# MEGA2560_Rev3e_1.net
KiCad netlist of a schematic drawn in Altium Designer
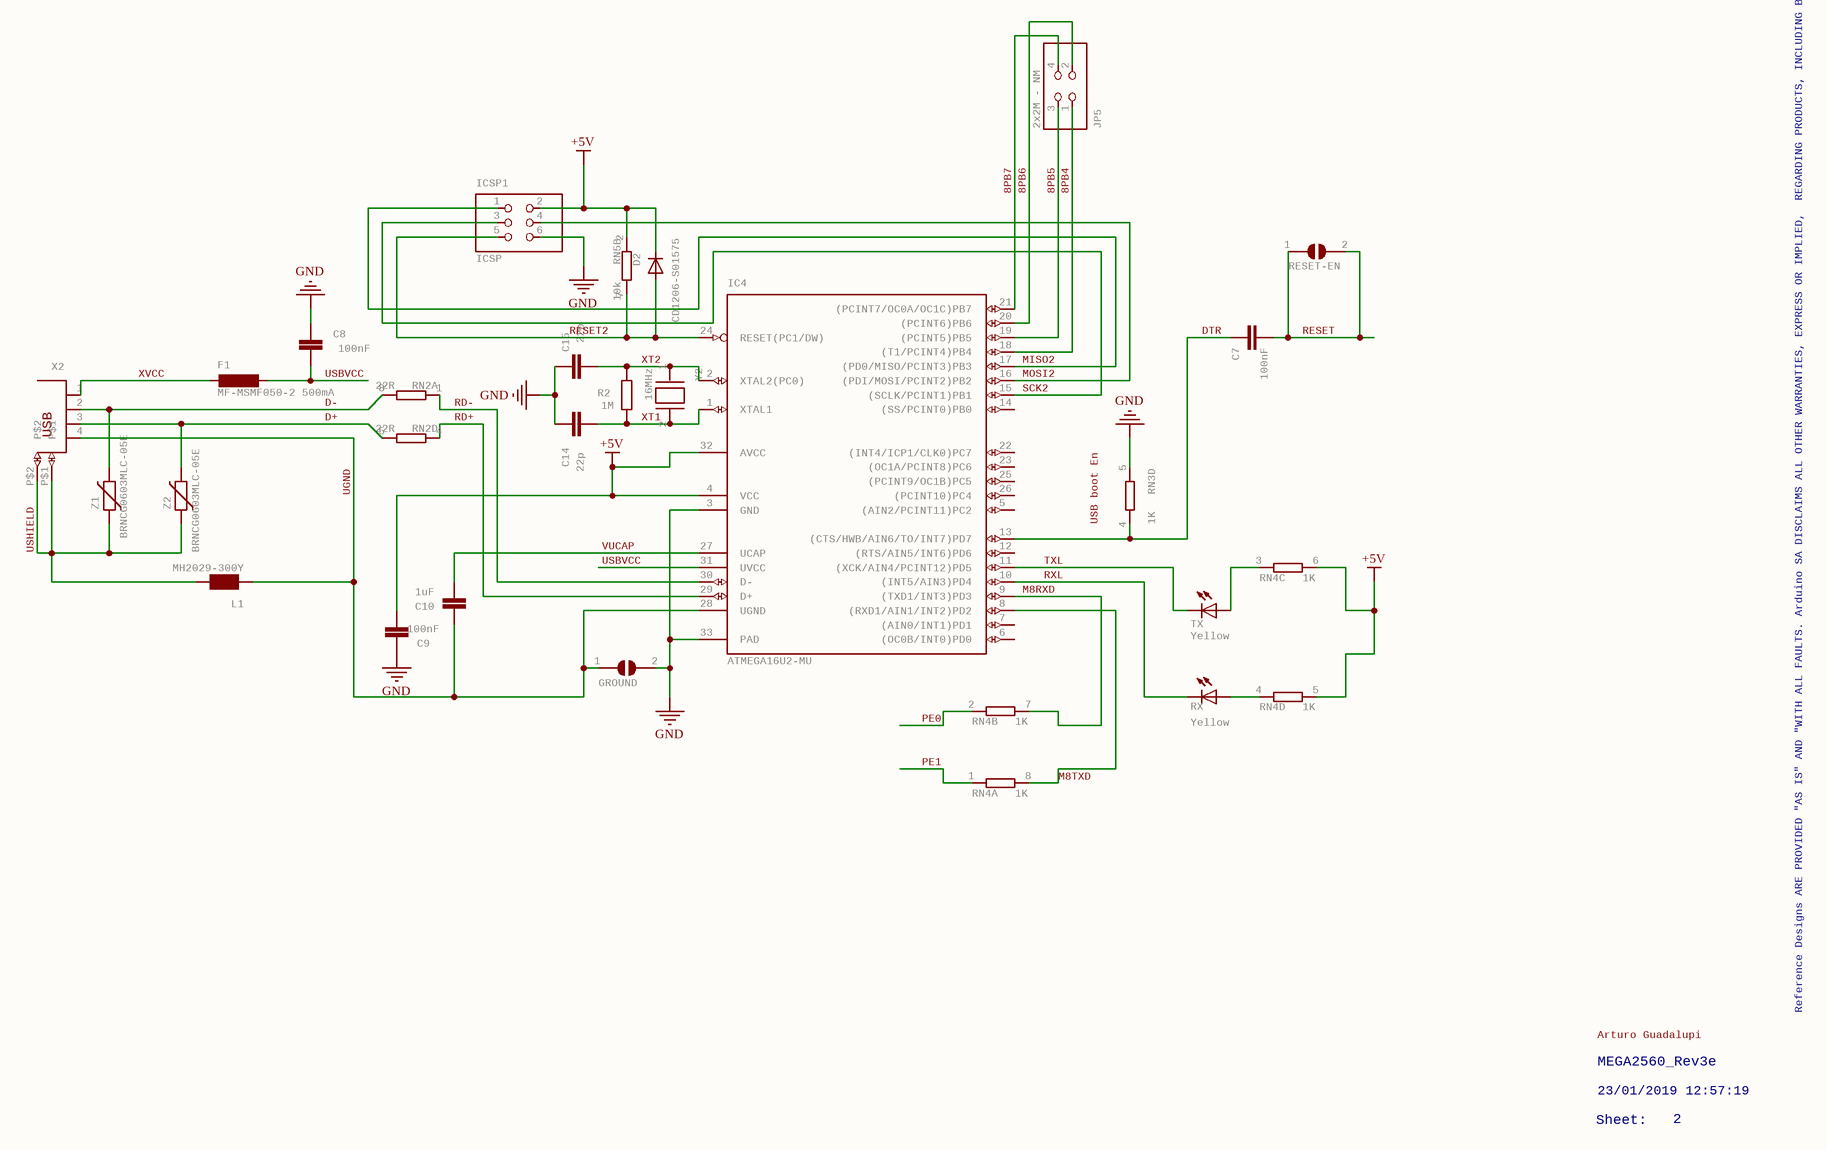
[diagram p0: MEGA2560_Rev3e_1.SchDoc]

(export (version "E")
  (design (tool "Eeschema 10.0.6"))
  (components
    (comp (ref "C7")
      (value "100nF")
      (footprint "C0603-ROUND")
      (description "100nF 0603 50V")
      (fields (field (name "PART_NUMBER") "cl10b104kbnc"))
      (libsource (lib "Condensatori") (part "0015_100NF_0603"))
    )
    (comp (ref "C8")
      (value "100nF")
      (footprint "C0603-ROUND")
      (description "100nF 0603 50V")
      (fields (field (name "PART_NUMBER") "cl10b104kbnc"))
      (libsource (lib "Condensatori") (part "0015_100NF_0603"))
    )
    (comp (ref "C9")
      (value "100nF")
      (footprint "C0603-ROUND")
      (description "100nF 0603 50V")
      (fields (field (name "PART_NUMBER") "cl10b104kbnc"))
      (libsource (lib "") (part "0015_100NF_0603_1"))
    )
    (comp (ref "C10")
      (value "1uF")
      (footprint "C0603-ROUND")
      (description "1uF 0603")
      (fields (field (name "PART_NUMBER") "1uF_0603/GRM188R61E105KA12D"))
      (libsource (lib "Condensatori") (part "0006_1UF_0603/GRM188R61E105KA12D"))
    )
    (comp (ref "C14")
      (value "22p")
      (footprint "C0603-ROUND")
      (description "22pF 0603")
      (fields (field (name "PART_NUMBER") "22pF_0603"))
      (libsource (lib "Condensatori") (part "0014_22PF_0603"))
    )
    (comp (ref "C15")
      (value "22p")
      (footprint "C0603-ROUND")
      (description "22pF 0603")
      (fields (field (name "PART_NUMBER") "22pF_0603"))
      (libsource (lib "Condensatori") (part "0014_22PF_0603"))
    )
    (comp (ref "D2")
      (value "CD1206-S01575")
      (footprint "MINIMELF")
      (description "small-signal high-speed Switching Diodes   CD1206")
      (libsource (lib "Diodi") (part "0012_CD1206-S01575"))
    )
    (comp (ref "F1")
      (value "MF-MSMF050-2 500mA")
      (footprint "L1812")
      (description "500 mA Multifuse ï¿½ Polyfuse")
      (fields (field (name "PART_NUMBER") "MF-MSMF050-2"))
      (libsource (lib "Protezione") (part "0002_MF-MSMF050-2"))
    )
    (comp (ref "GROUND")
      (value "SJ")
      (footprint "SJ")
      (description "SMD solder JUMPER")
      (libsource (lib "jumper") (part "SJ"))
    )
    (comp (ref "IC4")
      (value "ATMEGA16U2-MU")
      (footprint "MLF32")
      (description "8-bit Microcontroller with 16K Bytes of ISP Flash and USB Controller   ATMEGA16U2-MUR")
      (fields (field (name "PART_NUMBER") "ATMEGA16U2-MUR"))
      (libsource (lib "IntegratedCircuits") (part "0007_ATMEGA16U2-MUR"))
    )
    (comp (ref "ICSP1")
      (value "ICSP")
      (footprint "2X03")
      (description "3x2 M V h 8,5 mm p2,54")
      (fields (field (name "PART_NUMBER") "PH254-203DF118A00V") (field (name "LIBRARYNAME") "Connettori"))
      (libsource (lib "Connettori") (part "0114_PH254-203DF118A00V"))
    )
    (comp (ref "JP5")
      (value "2x2M - NM")
      (footprint "2X02")
      (description "PIN HEADER")
      (libsource (lib "SmartPrj") (part "PINHD-2X2"))
    )
    (comp (ref "L1")
      (value "MH2029-300Y")
      (footprint "0805")
      (description "BLM21")
      (fields (field (name "PART_NUMBER") "BLM21PG300SN1D_/_MH2029-300Y"))
      (libsource (lib "Protezione") (part "0001_BLM21PG300SN1D_/_MH2029-300Y"))
    )
    (comp (ref "R2")
      (value "1M")
      (footprint "R0603-ROUND")
      (description "1M 0603")
      (fields (field (name "PART_NUMBER") "0603_1M") (field (name "LIBRARYNAME") "Resistenze"))
      (libsource (lib "Resistenze") (part "0004_0603_1M"))
    )
    (comp (ref "RESET-EN")
      (value "SJ")
      (footprint "SJ")
      (description "SMD solder JUMPER")
      (libsource (lib "jumper") (part "SJ"))
    )
    (comp (ref "RN2")
      (value "22R")
      (footprint "CAY16")
      (description "22R 064R")
      (fields
        (field (name "PART_NUMBER") "064R_22R_/_CAY16-220J4LF")
        (field (name "LIBRARYNAME") "Resistenze")
      )
      (libsource (lib "Resistenze") (part "0003_064R_22R_/_CAY16-220J4LF"))
    )
    (comp (ref "RN3")
      (value "1K")
      (footprint "CAY16")
      (description "1K 064R")
      (fields
        (field (name "PART_NUMBER") "064R_1K_/_CAY16-102J4LF")
        (field (name "LIBRARYNAME") "Resistenze")
      )
      (libsource (lib "Resistenze") (part "0005_064R_1K_/_CAY16-102J4LF"))
    )
    (comp (ref "RN4")
      (value "1K")
      (footprint "CAY16")
      (description "1K 064R")
      (fields
        (field (name "PART_NUMBER") "064R_1K_/_CAY16-102J4LF")
        (field (name "LIBRARYNAME") "Resistenze")
      )
      (libsource (lib "Resistenze") (part "0005_064R_1K_/_CAY16-102J4LF"))
    )
    (comp (ref "RN5")
      (value "10k")
      (footprint "CAY16")
      (description "10K 064 R")
      (fields
        (field (name "PART_NUMBER") "064R_10K_/_CAY16-103J4LF")
        (field (name "LIBRARYNAME") "Resistenze")
      )
      (libsource (lib "Resistenze") (part "0016_064R_10K_/_CAY16-103J4LF"))
    )
    (comp (ref "RX")
      (value "Yellow")
      (footprint "CHIPLED_0805")
      (description "LED YELLOW - SMD - 0805")
      (fields (field (name "PART_NUMBER") "KPT-2012YC"))
      (libsource (lib "Opto") (part "0044_KPT-2012YC"))
    )
    (comp (ref "TX")
      (value "Yellow")
      (footprint "CHIPLED_0805")
      (description "LED YELLOW - SMD - 0805")
      (fields (field (name "PART_NUMBER") "KPT-2012YC"))
      (libsource (lib "Opto") (part "0044_KPT-2012YC"))
    )
    (comp (ref "X2")
      (value "0056_USB-B-S-RA-WT-SPCC")
      (footprint "PN61729")
      (description "USB - B")
      (fields
        (field (name "USB") "USB")
        (field (name "PART_NUMBER") "USB-B-S-RA-WT-SPCC")
        (field (name "LIBRARYNAME") "Connettori")
      )
      (libsource (lib "Connettori") (part "0056_USB-B-S-RA-WT-SPCC"))
    )
    (comp (ref "Y2")
      (value "16MHz")
      (footprint "QS")
      (description "16MHz THT")
      (fields
        (field (name "PART_NUMBER") "P011052006 16M/FTX16M20S")
        (field (name "LIBRARYNAME") "Cristalli")
      )
      (libsource (lib "Cristalli") (part "0019_P011052006_16M"))
    )
    (comp (ref "Z1")
      (value "BRNCG0603MLC-05E")
      (footprint "CT/CN0603")
      (description "CG0603MLC-05E")
      (libsource (lib "Protezione") (part "0010_BRNCG0603MLC-05E"))
    )
    (comp (ref "Z2")
      (value "BRNCG0603MLC-05E")
      (footprint "CT/CN0603")
      (description "CG0603MLC-05E")
      (libsource (lib "Protezione") (part "0010_BRNCG0603MLC-05E"))
    )
  )
  (nets
    (net (code "1") (name "+5V") (class "Default")
      (node (ref "C9") (pin "1") (pinfunction "1_1") (pintype "passive"))
      (node (ref "D2") (pin "C") (pinfunction "C_C") (pintype "passive"))
      (node (ref "IC4") (pin "32") (pinfunction "AVCC_32") (pintype "power_in"))
      (node (ref "IC4") (pin "4") (pinfunction "VCC_4") (pintype "power_in"))
      (node (ref "ICSP1") (pin "2") (pinfunction "2_2") (pintype "passive"))
      (node (ref "RN4") (pin "5") (pinfunction "2_5") (pintype "passive"))
      (node (ref "RN4") (pin "6") (pinfunction "2_6") (pintype "passive"))
      (node (ref "RN5") (pin "2") (pinfunction "1_2") (pintype "passive"))
    )
    (net (code "2") (name "/8PB4") (class "Default")
      (node (ref "IC4") (pin "18") (pinfunction "(T1/PCINT4)PB4_18") (pintype "bidirectional"))
      (node (ref "JP5") (pin "1") (pinfunction "1_1") (pintype "passive"))
    )
    (net (code "3") (name "/8PB5") (class "Default")
      (node (ref "IC4") (pin "19") (pinfunction "(PCINT5)PB5_19") (pintype "bidirectional"))
      (node (ref "JP5") (pin "3") (pinfunction "3_3") (pintype "passive"))
    )
    (net (code "4") (name "/8PB6") (class "Default")
      (node (ref "IC4") (pin "20") (pinfunction "(PCINT6)PB6_20") (pintype "bidirectional"))
      (node (ref "JP5") (pin "2") (pinfunction "2_2") (pintype "passive"))
    )
    (net (code "5") (name "/8PB7") (class "Default")
      (node (ref "IC4") (pin "21") (pinfunction "(PCINT7/OC0A/OC1C)PB7_21") (pintype "bidirectional"))
      (node (ref "JP5") (pin "4") (pinfunction "4_4") (pintype "passive"))
    )
    (net (code "6") (name "/D+") (class "Default")
      (node (ref "RN2") (pin "5") (pinfunction "2_5") (pintype "passive"))
      (node (ref "X2") (pin "3") (pinfunction "3_3") (pintype "bidirectional"))
      (node (ref "Z2") (pin "2") (pinfunction "2_2") (pintype "passive"))
    )
    (net (code "7") (name "/D-") (class "Default")
      (node (ref "RN2") (pin "8") (pinfunction "2_8") (pintype "passive"))
      (node (ref "X2") (pin "2") (pinfunction "2_2") (pintype "bidirectional"))
      (node (ref "Z1") (pin "2") (pinfunction "2_2") (pintype "passive"))
    )
    (net (code "8") (name "/DTR") (class "Default")
      (node (ref "C7") (pin "1") (pinfunction "1_1") (pintype "passive"))
      (node (ref "IC4") (pin "13") (pinfunction "(CTS/HWB/AIN6/TO/INT7)PD7_13") (pintype "bidirectional"))
      (node (ref "RN3") (pin "4") (pinfunction "1_4") (pintype "passive"))
    )
    (net (code "9") (name "/M8RXD") (class "Default")
      (node (ref "IC4") (pin "9") (pinfunction "(TXD1/INT3)PD3_9") (pintype "bidirectional"))
      (node (ref "RN4") (pin "7") (pinfunction "2_7") (pintype "passive"))
    )
    (net (code "10") (name "/M8TXD") (class "Default")
      (node (ref "IC4") (pin "8") (pinfunction "(RXD1/AIN1/INT2)PD2_8") (pintype "bidirectional"))
      (node (ref "RN4") (pin "8") (pinfunction "2_8") (pintype "passive"))
    )
    (net (code "11") (name "/MISO2") (class "Default")
      (node (ref "IC4") (pin "17") (pinfunction "(PD0/MISO/PCINT3)PB3_17") (pintype "bidirectional"))
      (node (ref "ICSP1") (pin "1") (pinfunction "1_1") (pintype "passive"))
    )
    (net (code "12") (name "/MOSI2") (class "Default")
      (node (ref "IC4") (pin "16") (pinfunction "(PDI/MOSI/PCINT2)PB2_16") (pintype "bidirectional"))
      (node (ref "ICSP1") (pin "4") (pinfunction "4_4") (pintype "passive"))
    )
    (net (code "13") (name "/PE0") (class "Default")
      (node (ref "RN4") (pin "2") (pinfunction "1_2") (pintype "passive"))
    )
    (net (code "14") (name "/PE1") (class "Default")
      (node (ref "RN4") (pin "1") (pinfunction "1_1") (pintype "passive"))
    )
    (net (code "15") (name "/RD+") (class "Default")
      (node (ref "IC4") (pin "29") (pinfunction "D+_29") (pintype "bidirectional"))
      (node (ref "RN2") (pin "4") (pinfunction "1_4") (pintype "passive"))
    )
    (net (code "16") (name "/RD-") (class "Default")
      (node (ref "IC4") (pin "30") (pinfunction "D-_30") (pintype "bidirectional"))
      (node (ref "RN2") (pin "1") (pinfunction "1_1") (pintype "passive"))
    )
    (net (code "17") (name "/RESET") (class "Default")
      (node (ref "C7") (pin "2") (pinfunction "2_2") (pintype "passive"))
      (node (ref "RESET-EN") (pin "1") (pinfunction "1_1") (pintype "passive"))
      (node (ref "RESET-EN") (pin "2") (pinfunction "2_2") (pintype "passive"))
    )
    (net (code "18") (name "/RESET2") (class "Default")
      (node (ref "D2") (pin "A") (pinfunction "A_A") (pintype "passive"))
      (node (ref "IC4") (pin "24") (pinfunction "RESET(PC1/DW)_24") (pintype "input"))
      (node (ref "ICSP1") (pin "5") (pinfunction "5_5") (pintype "passive"))
      (node (ref "RN5") (pin "7") (pinfunction "2_7") (pintype "passive"))
    )
    (net (code "19") (name "/RXL") (class "Default")
      (node (ref "IC4") (pin "10") (pinfunction "(INT5/AIN3)PD4_10") (pintype "bidirectional"))
      (node (ref "RX") (pin "C") (pinfunction "C_C") (pintype "passive"))
    )
    (net (code "20") (name "/SCK2") (class "Default")
      (node (ref "IC4") (pin "15") (pinfunction "(SCLK/PCINT1)PB1_15") (pintype "bidirectional"))
      (node (ref "ICSP1") (pin "3") (pinfunction "3_3") (pintype "passive"))
    )
    (net (code "21") (name "/TXL") (class "Default")
      (node (ref "IC4") (pin "11") (pinfunction "(XCK/AIN4/PCINT12)PD5_11") (pintype "bidirectional"))
      (node (ref "TX") (pin "C") (pinfunction "C_C") (pintype "passive"))
    )
    (net (code "22") (name "/UGND") (class "Default")
      (node (ref "C10") (pin "2") (pinfunction "2_2") (pintype "passive"))
      (node (ref "GROUND") (pin "1") (pinfunction "1_1") (pintype "passive"))
      (node (ref "IC4") (pin "28") (pinfunction "UGND_28") (pintype "power_in"))
      (node (ref "L1") (pin "1") (pinfunction "1_1") (pintype "passive"))
      (node (ref "X2") (pin "4") (pinfunction "4_4") (pintype "bidirectional"))
    )
    (net (code "23") (name "/USBVCC") (class "Default")
      (node (ref "C8") (pin "1") (pinfunction "1_1") (pintype "passive"))
      (node (ref "F1") (pin "1") (pinfunction "1_1") (pintype "passive"))
      (node (ref "IC4") (pin "31") (pinfunction "UVCC_31") (pintype "power_in"))
    )
    (net (code "24") (name "/USHIELD") (class "Default")
      (node (ref "L1") (pin "2") (pinfunction "2_2") (pintype "passive"))
      (node (ref "X2") (pin "P$1") (pinfunction "P$1_P$1") (pintype "bidirectional"))
      (node (ref "X2") (pin "P$2") (pinfunction "P$2_P$2") (pintype "bidirectional"))
      (node (ref "Z1") (pin "1") (pinfunction "1_1") (pintype "passive"))
      (node (ref "Z2") (pin "1") (pinfunction "1_1") (pintype "passive"))
    )
    (net (code "25") (name "/VUCAP") (class "Default")
      (node (ref "C10") (pin "1") (pinfunction "1_1") (pintype "passive"))
      (node (ref "IC4") (pin "27") (pinfunction "UCAP_27") (pintype "passive"))
    )
    (net (code "26") (name "/XT1") (class "Default")
      (node (ref "C14") (pin "1") (pinfunction "1_1") (pintype "passive"))
      (node (ref "IC4") (pin "1") (pinfunction "XTAL1_1") (pintype "bidirectional"))
      (node (ref "R2") (pin "1") (pinfunction "1_1") (pintype "passive"))
      (node (ref "Y2") (pin "2") (pinfunction "2_2") (pintype "passive"))
    )
    (net (code "27") (name "/XT2") (class "Default")
      (node (ref "C15") (pin "1") (pinfunction "1_1") (pintype "passive"))
      (node (ref "IC4") (pin "2") (pinfunction "XTAL2(PC0)_2") (pintype "bidirectional"))
      (node (ref "R2") (pin "2") (pinfunction "2_2") (pintype "passive"))
      (node (ref "Y2") (pin "1") (pinfunction "1_1") (pintype "passive"))
    )
    (net (code "28") (name "/XVCC") (class "Default")
      (node (ref "F1") (pin "2") (pinfunction "2_2") (pintype "passive"))
      (node (ref "X2") (pin "1") (pinfunction "1_1") (pintype "bidirectional"))
    )
    (net (code "29") (name "GND") (class "Default")
      (node (ref "C14") (pin "2") (pinfunction "2_2") (pintype "passive"))
      (node (ref "C15") (pin "2") (pinfunction "2_2") (pintype "passive"))
      (node (ref "C8") (pin "2") (pinfunction "2_2") (pintype "passive"))
      (node (ref "C9") (pin "2") (pinfunction "2_2") (pintype "passive"))
      (node (ref "GROUND") (pin "2") (pinfunction "2_2") (pintype "passive"))
      (node (ref "IC4") (pin "3") (pinfunction "GND_3") (pintype "power_in"))
      (node (ref "IC4") (pin "33") (pinfunction "PAD_33") (pintype "power_in"))
      (node (ref "ICSP1") (pin "6") (pinfunction "6_6") (pintype "passive"))
      (node (ref "RN3") (pin "5") (pinfunction "2_5") (pintype "passive"))
    )
    (net (code "30") (name "Net-(RN4C-1)") (class "Default")
      (node (ref "RN4") (pin "3") (pinfunction "1_3") (pintype "passive"))
      (node (ref "TX") (pin "A") (pinfunction "A_A") (pintype "passive"))
    )
    (net (code "31") (name "Net-(RN4D-1)") (class "Default")
      (node (ref "RN4") (pin "4") (pinfunction "1_4") (pintype "passive"))
      (node (ref "RX") (pin "A") (pinfunction "A_A") (pintype "passive"))
    )
    (net (code "32") (name "unconnected-(IC4-(AIN0{slash}INT1)PD1-Pad7)") (class "Default")
      (node (ref "IC4") (pin "7") (pinfunction "(AIN0/INT1)PD1_7") (pintype "bidirectional"))
    )
    (net (code "33") (name "unconnected-(IC4-(AIN2{slash}PCINT11)PC2-Pad5)") (class "Default")
      (node (ref "IC4") (pin "5") (pinfunction "(AIN2/PCINT11)PC2_5") (pintype "bidirectional"))
    )
    (net (code "34") (name "unconnected-(IC4-(INT4{slash}ICP1{slash}CLK0)PC7-Pad22)") (class "Default")
      (node (ref "IC4") (pin "22") (pinfunction "(INT4/ICP1/CLK0)PC7_22") (pintype "bidirectional"))
    )
    (net (code "35") (name "unconnected-(IC4-(OC0B{slash}INT0)PD0-Pad6)") (class "Default")
      (node (ref "IC4") (pin "6") (pinfunction "(OC0B/INT0)PD0_6") (pintype "bidirectional"))
    )
    (net (code "36") (name "unconnected-(IC4-(OC1A{slash}PCINT8)PC6-Pad23)") (class "Default")
      (node (ref "IC4") (pin "23") (pinfunction "(OC1A/PCINT8)PC6_23") (pintype "bidirectional"))
    )
    (net (code "37") (name "unconnected-(IC4-(PCINT9{slash}OC1B)PC5-Pad25)") (class "Default")
      (node (ref "IC4") (pin "25") (pinfunction "(PCINT9/OC1B)PC5_25") (pintype "bidirectional"))
    )
    (net (code "38") (name "unconnected-(IC4-(PCINT10)PC4-Pad26)") (class "Default")
      (node (ref "IC4") (pin "26") (pinfunction "(PCINT10)PC4_26") (pintype "bidirectional"))
    )
    (net (code "39") (name "unconnected-(IC4-(RTS{slash}AIN5{slash}INT6)PD6-Pad12)") (class "Default")
      (node (ref "IC4") (pin "12") (pinfunction "(RTS/AIN5/INT6)PD6_12") (pintype "bidirectional"))
    )
    (net (code "40") (name "unconnected-(IC4-(SS{slash}PCINT0)PB0-Pad14)") (class "Default")
      (node (ref "IC4") (pin "14") (pinfunction "(SS/PCINT0)PB0_14") (pintype "bidirectional"))
    )
  )
)
